# ALINHAMENTO_UNIC.net
KiCad netlist of a schematic drawn in EAGLE
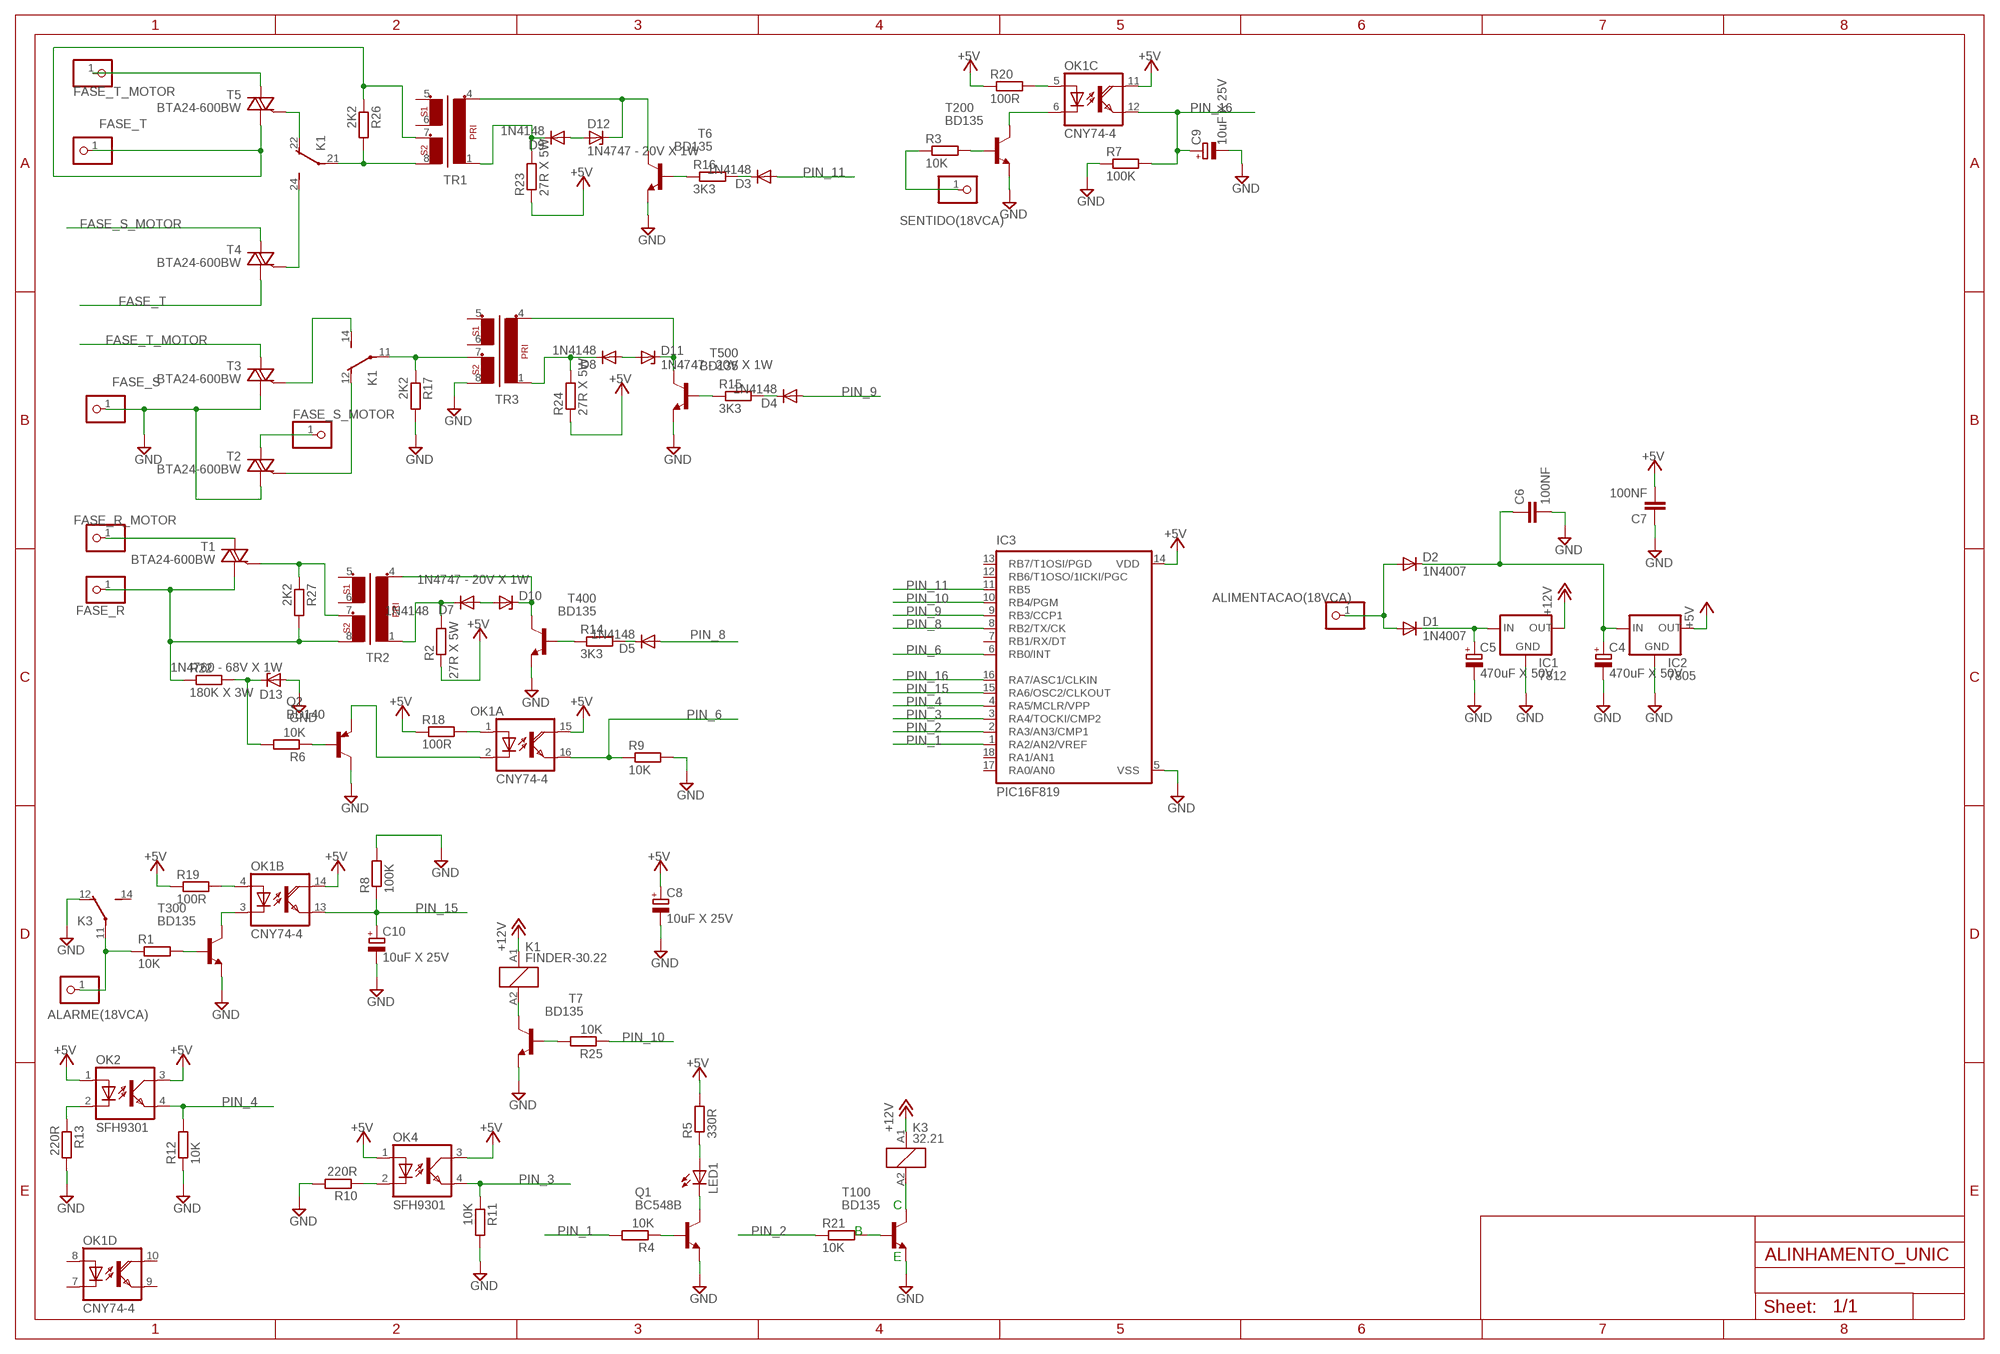
[diagram p0: schematic, sheet 1]

(export (version "E")
  (design (tool "Eeschema 10.0.6"))
  (components
    (comp (ref "ALARME(18VCA)")
      (value "PINHD-1X1")
      (footprint "eagle-import:1X01")
      (libsource (lib "eagle-import") (part "PINHD-1X1"))
    )
    (comp (ref "ALIMENTACAO(18VCA)")
      (value "PINHD-1X1")
      (footprint "eagle-import:1X01")
      (libsource (lib "eagle-import") (part "PINHD-1X1"))
    )
    (comp (ref "C4")
      (value "470uF X 50V")
      (footprint "eagle-import:E5-13")
      (libsource (lib "eagle-import") (part "CPOL-EUE5-13"))
    )
    (comp (ref "C5")
      (value "470uF X 50V")
      (footprint "eagle-import:E5-13")
      (libsource (lib "eagle-import") (part "CPOL-EUE5-13"))
    )
    (comp (ref "C6")
      (value "100NF")
      (footprint "eagle-import:C050-025X075")
      (libsource (lib "eagle-import") (part "C-EU050-025X075"))
    )
    (comp (ref "C7")
      (value "100NF")
      (footprint "eagle-import:C050-025X075")
      (libsource (lib "eagle-import") (part "C-EU050-025X075"))
    )
    (comp (ref "C8")
      (value "10uF X 25V")
      (footprint "eagle-import:E2-5")
      (libsource (lib "eagle-import") (part "CPOL-EUE2-5"))
    )
    (comp (ref "C9")
      (value "10uF X 25V")
      (footprint "eagle-import:E2-5")
      (libsource (lib "eagle-import") (part "CPOL-EUE2-5"))
    )
    (comp (ref "C10")
      (value "10uF X 25V")
      (footprint "eagle-import:E2-5")
      (libsource (lib "eagle-import") (part "CPOL-EUE2-5"))
    )
    (comp (ref "D1")
      (value "1N4007")
      (footprint "eagle-import:DO41-10")
      (libsource (lib "eagle-import") (part "1N4004"))
    )
    (comp (ref "D2")
      (value "1N4007")
      (footprint "eagle-import:DO41-10")
      (libsource (lib "eagle-import") (part "1N4004"))
    )
    (comp (ref "D3")
      (value "1N4148")
      (footprint "eagle-import:DO35-10")
      (libsource (lib "eagle-import") (part "1N4148DO35-10"))
    )
    (comp (ref "D4")
      (value "1N4148")
      (footprint "eagle-import:DO35-10")
      (libsource (lib "eagle-import") (part "1N4148DO35-10"))
    )
    (comp (ref "D5")
      (value "1N4148")
      (footprint "eagle-import:DO35-10")
      (libsource (lib "eagle-import") (part "1N4148DO35-10"))
    )
    (comp (ref "D7")
      (value "1N4148")
      (footprint "eagle-import:DO35-10")
      (libsource (lib "eagle-import") (part "1N4148DO35-10"))
    )
    (comp (ref "D8")
      (value "1N4148")
      (footprint "eagle-import:DO35-10")
      (libsource (lib "eagle-import") (part "1N4148DO35-10"))
    )
    (comp (ref "D9")
      (value "1N4148")
      (footprint "eagle-import:DO35-10")
      (libsource (lib "eagle-import") (part "1N4148DO35-10"))
    )
    (comp (ref "D10")
      (value "1N4747 - 20V X 1W")
      (footprint "eagle-import:DO41Z10")
      (libsource (lib "eagle-import") (part "1N4728"))
    )
    (comp (ref "D11")
      (value "1N4747 - 20V X 1W")
      (footprint "eagle-import:DO41Z10")
      (libsource (lib "eagle-import") (part "1N4728"))
    )
    (comp (ref "D12")
      (value "1N4747 - 20V X 1W")
      (footprint "eagle-import:DO41Z10")
      (libsource (lib "eagle-import") (part "1N4728"))
    )
    (comp (ref "D13")
      (value "1N4760 - 68V X 1W")
      (footprint "eagle-import:DO41Z10")
      (libsource (lib "eagle-import") (part "1N4728"))
    )
    (comp (ref "FASE_R")
      (value "PINHD-1X1")
      (footprint "eagle-import:1X01")
      (libsource (lib "eagle-import") (part "PINHD-1X1"))
    )
    (comp (ref "FASE_R_MOTOR")
      (value "PINHD-1X1")
      (footprint "eagle-import:1X01")
      (libsource (lib "eagle-import") (part "PINHD-1X1"))
    )
    (comp (ref "FASE_S")
      (value "PINHD-1X1")
      (footprint "eagle-import:1X01")
      (libsource (lib "eagle-import") (part "PINHD-1X1"))
    )
    (comp (ref "FASE_S_MOTOR")
      (value "PINHD-1X1")
      (footprint "eagle-import:1X01")
      (libsource (lib "eagle-import") (part "PINHD-1X1"))
    )
    (comp (ref "FASE_T")
      (value "PINHD-1X1")
      (footprint "eagle-import:1X01")
      (libsource (lib "eagle-import") (part "PINHD-1X1"))
    )
    (comp (ref "FASE_T_MOTOR")
      (value "PINHD-1X1")
      (footprint "eagle-import:1X01")
      (libsource (lib "eagle-import") (part "PINHD-1X1"))
    )
    (comp (ref "IC1")
      (value "7812")
      (footprint "eagle-import:78MXXS")
      (libsource (lib "eagle-import") (part "78MXXS"))
    )
    (comp (ref "IC2")
      (value "7805")
      (footprint "eagle-import:78MXXS")
      (libsource (lib "eagle-import") (part "78MXXS"))
    )
    (comp (ref "IC3")
      (value "PIC16F819")
      (footprint "eagle-import:DIL18")
      (libsource (lib "eagle-import") (part "PIC16F627P"))
    )
    (comp (ref "K1")
      (value "FINDER-30.22")
      (footprint "eagle-import:FINDER-30.22")
      (libsource (lib "eagle-import") (part "FINDER-30.22"))
    )
    (comp (ref "K3")
      (value "32.21")
      (footprint "eagle-import:RP51")
      (libsource (lib "eagle-import") (part "32.21"))
    )
    (comp (ref "LED1")
      (value "LED5MM")
      (footprint "eagle-import:LED5MM")
      (libsource (lib "eagle-import") (part "LED5MM"))
    )
    (comp (ref "OK1")
      (value "CNY74-4")
      (footprint "eagle-import:DIL16")
      (libsource (lib "eagle-import") (part "ILQ30"))
    )
    (comp (ref "OK2")
      (value "SFH9301")
      (footprint "eagle-import:SFH9301")
      (libsource (lib "eagle-import") (part "SFH9301"))
    )
    (comp (ref "OK4")
      (value "SFH9301")
      (footprint "eagle-import:SFH9301")
      (libsource (lib "eagle-import") (part "SFH9301"))
    )
    (comp (ref "Q1")
      (value "BC548B")
      (footprint "eagle-import:TO92-EBC")
      (libsource (lib "eagle-import") (part "BC548B"))
    )
    (comp (ref "Q2")
      (value "BD140")
      (footprint "eagle-import:TO126")
      (libsource (lib "eagle-import") (part "BD140"))
    )
    (comp (ref "R1")
      (value "10K")
      (footprint "eagle-import:0207_10")
      (libsource (lib "eagle-import") (part "R-EU_0207/10"))
    )
    (comp (ref "R2")
      (value "27R X 5W")
      (footprint "eagle-import:0617_22")
      (libsource (lib "eagle-import") (part "R-EU_0617/22"))
    )
    (comp (ref "R3")
      (value "10K")
      (footprint "eagle-import:0207_10")
      (libsource (lib "eagle-import") (part "R-EU_0207/10"))
    )
    (comp (ref "R4")
      (value "10K")
      (footprint "eagle-import:0207_10")
      (libsource (lib "eagle-import") (part "R-EU_0207/10"))
    )
    (comp (ref "R5")
      (value "330R")
      (footprint "eagle-import:0207_10")
      (libsource (lib "eagle-import") (part "R-EU_0207/10"))
    )
    (comp (ref "R6")
      (value "10K")
      (footprint "eagle-import:0207_10")
      (libsource (lib "eagle-import") (part "R-EU_0207/10"))
    )
    (comp (ref "R7")
      (value "100K")
      (footprint "eagle-import:0207_10")
      (libsource (lib "eagle-import") (part "R-EU_0207/10"))
    )
    (comp (ref "R8")
      (value "100K")
      (footprint "eagle-import:0207_10")
      (libsource (lib "eagle-import") (part "R-EU_0207/10"))
    )
    (comp (ref "R9")
      (value "10K")
      (footprint "eagle-import:0207_10")
      (libsource (lib "eagle-import") (part "R-EU_0207/10"))
    )
    (comp (ref "R10")
      (value "220R")
      (footprint "eagle-import:0207_10")
      (libsource (lib "eagle-import") (part "R-EU_0207/10"))
    )
    (comp (ref "R11")
      (value "10K")
      (footprint "eagle-import:0207_10")
      (libsource (lib "eagle-import") (part "R-EU_0207/10"))
    )
    (comp (ref "R12")
      (value "10K")
      (footprint "eagle-import:0207_10")
      (libsource (lib "eagle-import") (part "R-EU_0207/10"))
    )
    (comp (ref "R13")
      (value "220R")
      (footprint "eagle-import:0207_10")
      (libsource (lib "eagle-import") (part "R-EU_0207/10"))
    )
    (comp (ref "R14")
      (value "3K3")
      (footprint "eagle-import:0207_10")
      (libsource (lib "eagle-import") (part "R-EU_0207/10"))
    )
    (comp (ref "R15")
      (value "3K3")
      (footprint "eagle-import:0207_10")
      (libsource (lib "eagle-import") (part "R-EU_0207/10"))
    )
    (comp (ref "R16")
      (value "3K3")
      (footprint "eagle-import:0207_10")
      (libsource (lib "eagle-import") (part "R-EU_0207/10"))
    )
    (comp (ref "R17")
      (value "2K2")
      (footprint "eagle-import:0207_10")
      (libsource (lib "eagle-import") (part "R-EU_0207/10"))
    )
    (comp (ref "R18")
      (value "100R")
      (footprint "eagle-import:0207_10")
      (libsource (lib "eagle-import") (part "R-EU_0207/10"))
    )
    (comp (ref "R19")
      (value "100R")
      (footprint "eagle-import:0207_10")
      (libsource (lib "eagle-import") (part "R-EU_0207/10"))
    )
    (comp (ref "R20")
      (value "100R")
      (footprint "eagle-import:0207_10")
      (libsource (lib "eagle-import") (part "R-EU_0207/10"))
    )
    (comp (ref "R21")
      (value "10K")
      (footprint "eagle-import:0207_10")
      (libsource (lib "eagle-import") (part "R-EU_0207/10"))
    )
    (comp (ref "R22")
      (value "180K X 3W")
      (footprint "eagle-import:0617_22")
      (libsource (lib "eagle-import") (part "R-EU_0617/22"))
    )
    (comp (ref "R23")
      (value "27R X 5W")
      (footprint "eagle-import:0617_22")
      (libsource (lib "eagle-import") (part "R-EU_0617/22"))
    )
    (comp (ref "R24")
      (value "27R X 5W")
      (footprint "eagle-import:0617_22")
      (libsource (lib "eagle-import") (part "R-EU_0617/22"))
    )
    (comp (ref "R25")
      (value "10K")
      (footprint "eagle-import:0207_10")
      (libsource (lib "eagle-import") (part "R-EU_0207/10"))
    )
    (comp (ref "R26")
      (value "2K2")
      (footprint "eagle-import:0207_10")
      (libsource (lib "eagle-import") (part "R-EU_0207/10"))
    )
    (comp (ref "R27")
      (value "2K2")
      (footprint "eagle-import:0207_10")
      (libsource (lib "eagle-import") (part "R-EU_0207/10"))
    )
    (comp (ref "SENTIDO(18VCA)")
      (value "PINHD-1X1")
      (footprint "eagle-import:1X01")
      (libsource (lib "eagle-import") (part "PINHD-1X1"))
    )
    (comp (ref "T1")
      (value "BTA24-600BW")
      (footprint "eagle-import:TOP3S-1")
      (libsource (lib "eagle-import") (part "BTA26-V"))
    )
    (comp (ref "T2")
      (value "BTA24-600BW")
      (footprint "eagle-import:TOP3S-1")
      (libsource (lib "eagle-import") (part "BTA26-V"))
    )
    (comp (ref "T3")
      (value "BTA24-600BW")
      (footprint "eagle-import:TOP3S-1")
      (libsource (lib "eagle-import") (part "BTA26-V"))
    )
    (comp (ref "T4")
      (value "BTA24-600BW")
      (footprint "eagle-import:TOP3S-1")
      (libsource (lib "eagle-import") (part "BTA26-V"))
    )
    (comp (ref "T5")
      (value "BTA24-600BW")
      (footprint "eagle-import:TOP3S-1")
      (libsource (lib "eagle-import") (part "BTA26-V"))
    )
    (comp (ref "T6")
      (value "BD135")
      (footprint "eagle-import:TO126")
      (libsource (lib "eagle-import") (part "BD139"))
    )
    (comp (ref "T7")
      (value "BD135")
      (footprint "eagle-import:TO126")
      (libsource (lib "eagle-import") (part "BD139"))
    )
    (comp (ref "T100")
      (value "BD135")
      (footprint "eagle-import:TO126")
      (libsource (lib "eagle-import") (part "BD139"))
    )
    (comp (ref "T200")
      (value "BD135")
      (footprint "eagle-import:TO126")
      (libsource (lib "eagle-import") (part "BD139"))
    )
    (comp (ref "T300")
      (value "BD135")
      (footprint "eagle-import:TO126")
      (libsource (lib "eagle-import") (part "BD139"))
    )
    (comp (ref "T400")
      (value "BD135")
      (footprint "eagle-import:TO126")
      (libsource (lib "eagle-import") (part "BD139"))
    )
    (comp (ref "T500")
      (value "BD135")
      (footprint "eagle-import:TO126")
      (libsource (lib "eagle-import") (part "BD139"))
    )
    (comp (ref "TR1")
      (value "EE20-2")
      (footprint "eagle-import:EE20-2")
      (libsource (lib "eagle-import") (part "EE20-2"))
    )
    (comp (ref "TR2")
      (value "EE20-2")
      (footprint "eagle-import:EE20-2")
      (libsource (lib "eagle-import") (part "EE20-2"))
    )
    (comp (ref "TR3")
      (value "EE20-2")
      (footprint "eagle-import:EE20-2")
      (libsource (lib "eagle-import") (part "EE20-2"))
    )
  )
  (nets
    (net (code "1") (name "+5V") (class "Default")
      (node (ref "C7") (pin "2") (pinfunction "2_2") (pintype "passive"))
      (node (ref "C8") (pin "+") (pinfunction "+_+") (pintype "passive"))
      (node (ref "IC2") (pin "OUT") (pinfunction "OUT_OUT") (pintype "passive"))
      (node (ref "IC3") (pin "14") (pinfunction "VDD_14") (pintype "power_in"))
      (node (ref "OK1") (pin "11") (pinfunction "COL_11") (pintype "passive"))
      (node (ref "OK1") (pin "14") (pinfunction "COL_14") (pintype "passive"))
      (node (ref "OK1") (pin "15") (pinfunction "COL_15") (pintype "passive"))
      (node (ref "OK2") (pin "1") (pinfunction "A_1") (pintype "passive"))
      (node (ref "OK2") (pin "3") (pinfunction "COL_3") (pintype "passive"))
      (node (ref "OK4") (pin "1") (pinfunction "A_1") (pintype "passive"))
      (node (ref "OK4") (pin "3") (pinfunction "COL_3") (pintype "passive"))
      (node (ref "R18") (pin "1") (pinfunction "1_1") (pintype "passive"))
      (node (ref "R19") (pin "1") (pinfunction "1_1") (pintype "passive"))
      (node (ref "R2") (pin "1") (pinfunction "1_1") (pintype "passive"))
      (node (ref "R20") (pin "1") (pinfunction "1_1") (pintype "passive"))
      (node (ref "R23") (pin "1") (pinfunction "1_1") (pintype "passive"))
      (node (ref "R24") (pin "1") (pinfunction "1_1") (pintype "passive"))
      (node (ref "R5") (pin "2") (pinfunction "2_2") (pintype "passive"))
    )
    (net (code "2") (name "+12V") (class "Default")
      (node (ref "IC1") (pin "OUT") (pinfunction "OUT_OUT") (pintype "passive"))
      (node (ref "K1") (pin "A1") (pinfunction "1_A1") (pintype "passive"))
      (node (ref "K3") (pin "A1") (pinfunction "1_A1") (pintype "passive"))
    )
    (net (code "3") (name "/FASE_S_MOTOR") (class "Default")
      (node (ref "FASE_S_MOTOR") (pin "1") (pinfunction "1_1") (pintype "passive"))
      (node (ref "T2") (pin "A2") (pinfunction "A2_A2") (pintype "passive"))
      (node (ref "T4") (pin "A2") (pinfunction "A2_A2") (pintype "passive"))
    )
    (net (code "4") (name "/FASE_T") (class "Default")
      (node (ref "FASE_T") (pin "1") (pinfunction "1_1") (pintype "passive"))
      (node (ref "R26") (pin "1") (pinfunction "1_1") (pintype "passive"))
      (node (ref "T4") (pin "A1") (pinfunction "A1_A1") (pintype "passive"))
      (node (ref "T5") (pin "A1") (pinfunction "A1_A1") (pintype "passive"))
      (node (ref "TR1") (pin "7") (pinfunction "5_7") (pintype "passive"))
    )
    (net (code "5") (name "/FASE_T_MOTOR") (class "Default")
      (node (ref "FASE_T_MOTOR") (pin "1") (pinfunction "1_1") (pintype "passive"))
      (node (ref "T3") (pin "A2") (pinfunction "A2_A2") (pintype "passive"))
      (node (ref "T5") (pin "A2") (pinfunction "A2_A2") (pintype "passive"))
    )
    (net (code "6") (name "/PIN_1") (class "Default")
      (node (ref "IC3") (pin "1") (pinfunction "RA2/AN2/VREF_1") (pintype "bidirectional"))
      (node (ref "R4") (pin "2") (pinfunction "2_2") (pintype "passive"))
    )
    (net (code "7") (name "/PIN_2") (class "Default")
      (node (ref "IC3") (pin "2") (pinfunction "RA3/AN3/CMP1_2") (pintype "bidirectional"))
      (node (ref "R21") (pin "1") (pinfunction "1_1") (pintype "passive"))
    )
    (net (code "8") (name "/PIN_3") (class "Default")
      (node (ref "IC3") (pin "3") (pinfunction "RA4/TOCKI/CMP2_3") (pintype "bidirectional"))
      (node (ref "OK4") (pin "4") (pinfunction "EMIT_4") (pintype "passive"))
      (node (ref "R11") (pin "1") (pinfunction "1_1") (pintype "passive"))
    )
    (net (code "9") (name "/PIN_4") (class "Default")
      (node (ref "IC3") (pin "4") (pinfunction "RA5/MCLR/VPP_4") (pintype "input"))
      (node (ref "OK2") (pin "4") (pinfunction "EMIT_4") (pintype "passive"))
      (node (ref "R12") (pin "2") (pinfunction "2_2") (pintype "passive"))
    )
    (net (code "10") (name "/PIN_6") (class "Default")
      (node (ref "IC3") (pin "6") (pinfunction "RB0/INT_6") (pintype "bidirectional"))
      (node (ref "OK1") (pin "16") (pinfunction "EMI_16") (pintype "passive"))
      (node (ref "R9") (pin "1") (pinfunction "1_1") (pintype "passive"))
    )
    (net (code "11") (name "/PIN_8") (class "Default")
      (node (ref "D5") (pin "A") (pinfunction "A_A") (pintype "passive"))
      (node (ref "IC3") (pin "8") (pinfunction "RB2/TX/CK_8") (pintype "bidirectional"))
    )
    (net (code "12") (name "/PIN_9") (class "Default")
      (node (ref "D4") (pin "A") (pinfunction "A_A") (pintype "passive"))
      (node (ref "IC3") (pin "9") (pinfunction "RB3/CCP1_9") (pintype "bidirectional"))
    )
    (net (code "13") (name "/PIN_10") (class "Default")
      (node (ref "IC3") (pin "10") (pinfunction "RB4/PGM_10") (pintype "bidirectional"))
      (node (ref "R25") (pin "1") (pinfunction "1_1") (pintype "passive"))
    )
    (net (code "14") (name "/PIN_11") (class "Default")
      (node (ref "D3") (pin "A") (pinfunction "A_A") (pintype "passive"))
      (node (ref "IC3") (pin "11") (pinfunction "RB5_11") (pintype "bidirectional"))
    )
    (net (code "15") (name "/PIN_15") (class "Default")
      (node (ref "C10") (pin "+") (pinfunction "+_+") (pintype "passive"))
      (node (ref "IC3") (pin "15") (pinfunction "RA6/OSC2/CLKOUT_15") (pintype "bidirectional"))
      (node (ref "OK1") (pin "13") (pinfunction "EMI_13") (pintype "passive"))
      (node (ref "R8") (pin "1") (pinfunction "1_1") (pintype "passive"))
    )
    (net (code "16") (name "/PIN_16") (class "Default")
      (node (ref "C9") (pin "+") (pinfunction "+_+") (pintype "passive"))
      (node (ref "IC3") (pin "16") (pinfunction "RA7/ASC1/CLKIN_16") (pintype "bidirectional"))
      (node (ref "OK1") (pin "12") (pinfunction "EMI_12") (pintype "passive"))
      (node (ref "R7") (pin "2") (pinfunction "2_2") (pintype "passive"))
    )
    (net (code "17") (name "GND") (class "Default")
      (node (ref "C10") (pin "-") (pinfunction "-_-") (pintype "passive"))
      (node (ref "C4") (pin "-") (pinfunction "-_-") (pintype "passive"))
      (node (ref "C5") (pin "-") (pinfunction "-_-") (pintype "passive"))
      (node (ref "C6") (pin "2") (pinfunction "2_2") (pintype "passive"))
      (node (ref "C7") (pin "1") (pinfunction "1_1") (pintype "passive"))
      (node (ref "C8") (pin "-") (pinfunction "-_-") (pintype "passive"))
      (node (ref "C9") (pin "-") (pinfunction "-_-") (pintype "passive"))
      (node (ref "D13") (pin "A") (pinfunction "A_A") (pintype "passive"))
      (node (ref "FASE_S") (pin "1") (pinfunction "1_1") (pintype "passive"))
      (node (ref "IC1") (pin "GND") (pinfunction "GND_GND") (pintype "input"))
      (node (ref "IC2") (pin "GND") (pinfunction "GND_GND") (pintype "input"))
      (node (ref "IC3") (pin "5") (pinfunction "VSS_5") (pintype "power_in"))
      (node (ref "K3") (pin "12") (pinfunction "O_12") (pintype "passive"))
      (node (ref "Q1") (pin "E") (pinfunction "E_E") (pintype "passive"))
      (node (ref "Q2") (pin "2") (pinfunction "C_2") (pintype "passive"))
      (node (ref "R10") (pin "2") (pinfunction "2_2") (pintype "passive"))
      (node (ref "R11") (pin "2") (pinfunction "2_2") (pintype "passive"))
      (node (ref "R12") (pin "1") (pinfunction "1_1") (pintype "passive"))
      (node (ref "R13") (pin "2") (pinfunction "2_2") (pintype "passive"))
      (node (ref "R17") (pin "2") (pinfunction "2_2") (pintype "passive"))
      (node (ref "R7") (pin "1") (pinfunction "1_1") (pintype "passive"))
      (node (ref "R8") (pin "2") (pinfunction "2_2") (pintype "passive"))
      (node (ref "R9") (pin "2") (pinfunction "2_2") (pintype "passive"))
      (node (ref "T100") (pin "1") (pinfunction "E_1") (pintype "passive"))
      (node (ref "T2") (pin "A1") (pinfunction "A1_A1") (pintype "passive"))
      (node (ref "T200") (pin "1") (pinfunction "E_1") (pintype "passive"))
      (node (ref "T3") (pin "A1") (pinfunction "A1_A1") (pintype "passive"))
      (node (ref "T300") (pin "1") (pinfunction "E_1") (pintype "passive"))
      (node (ref "T400") (pin "1") (pinfunction "E_1") (pintype "passive"))
      (node (ref "T500") (pin "1") (pinfunction "E_1") (pintype "passive"))
      (node (ref "T6") (pin "1") (pinfunction "E_1") (pintype "passive"))
      (node (ref "T7") (pin "1") (pinfunction "E_1") (pintype "passive"))
      (node (ref "TR3") (pin "8") (pinfunction "6_8") (pintype "passive"))
    )
    (net (code "18") (name "Net-(ALIMENTACAO(18VCA)-Pad1)") (class "Default")
      (node (ref "ALIMENTACAO(18VCA)") (pin "1") (pinfunction "1_1") (pintype "passive"))
      (node (ref "D1") (pin "A") (pinfunction "A_A") (pintype "passive"))
      (node (ref "D2") (pin "A") (pinfunction "A_A") (pintype "passive"))
    )
    (net (code "19") (name "Net-(C4-Pad+)") (class "Default")
      (node (ref "C4") (pin "+") (pinfunction "+_+") (pintype "passive"))
      (node (ref "C6") (pin "1") (pinfunction "1_1") (pintype "passive"))
      (node (ref "D2") (pin "C") (pinfunction "C_C") (pintype "passive"))
      (node (ref "IC2") (pin "IN") (pinfunction "IN_IN") (pintype "input"))
    )
    (net (code "20") (name "Net-(C5-Pad+)") (class "Default")
      (node (ref "C5") (pin "+") (pinfunction "+_+") (pintype "passive"))
      (node (ref "D1") (pin "C") (pinfunction "C_C") (pintype "passive"))
      (node (ref "IC1") (pin "IN") (pinfunction "IN_IN") (pintype "input"))
    )
    (net (code "21") (name "Net-(D3-PadC)") (class "Default")
      (node (ref "D3") (pin "C") (pinfunction "C_C") (pintype "passive"))
      (node (ref "R16") (pin "2") (pinfunction "2_2") (pintype "passive"))
    )
    (net (code "22") (name "Net-(D4-PadC)") (class "Default")
      (node (ref "D4") (pin "C") (pinfunction "C_C") (pintype "passive"))
      (node (ref "R15") (pin "2") (pinfunction "2_2") (pintype "passive"))
    )
    (net (code "23") (name "Net-(D5-PadC)") (class "Default")
      (node (ref "D5") (pin "C") (pinfunction "C_C") (pintype "passive"))
      (node (ref "R14") (pin "2") (pinfunction "2_2") (pintype "passive"))
    )
    (net (code "24") (name "Net-(D7-PadC)") (class "Default")
      (node (ref "D7") (pin "C") (pinfunction "C_C") (pintype "passive"))
      (node (ref "R2") (pin "2") (pinfunction "2_2") (pintype "passive"))
      (node (ref "TR2") (pin "1") (pinfunction "1_1") (pintype "passive"))
    )
    (net (code "25") (name "Net-(D8-PadC)") (class "Default")
      (node (ref "D8") (pin "C") (pinfunction "C_C") (pintype "passive"))
      (node (ref "R24") (pin "2") (pinfunction "2_2") (pintype "passive"))
      (node (ref "TR3") (pin "1") (pinfunction "1_1") (pintype "passive"))
    )
    (net (code "26") (name "Net-(D9-PadC)") (class "Default")
      (node (ref "D9") (pin "C") (pinfunction "C_C") (pintype "passive"))
      (node (ref "R23") (pin "2") (pinfunction "2_2") (pintype "passive"))
      (node (ref "TR1") (pin "1") (pinfunction "1_1") (pintype "passive"))
    )
    (net (code "27") (name "Net-(D10-PadA)") (class "Default")
      (node (ref "D10") (pin "A") (pinfunction "A_A") (pintype "passive"))
      (node (ref "D7") (pin "A") (pinfunction "A_A") (pintype "passive"))
    )
    (net (code "28") (name "Net-(D11-PadA)") (class "Default")
      (node (ref "D11") (pin "A") (pinfunction "A_A") (pintype "passive"))
      (node (ref "D8") (pin "A") (pinfunction "A_A") (pintype "passive"))
    )
    (net (code "29") (name "Net-(D12-PadA)") (class "Default")
      (node (ref "D12") (pin "A") (pinfunction "A_A") (pintype "passive"))
      (node (ref "D9") (pin "A") (pinfunction "A_A") (pintype "passive"))
    )
    (net (code "30") (name "Net-(D13-PadC)") (class "Default")
      (node (ref "D13") (pin "C") (pinfunction "C_C") (pintype "passive"))
      (node (ref "R22") (pin "2") (pinfunction "2_2") (pintype "passive"))
      (node (ref "R6") (pin "2") (pinfunction "2_2") (pintype "passive"))
    )
    (net (code "31") (name "Net-(FASE_R_MOTOR-Pad1)") (class "Default")
      (node (ref "FASE_R_MOTOR") (pin "1") (pinfunction "1_1") (pintype "passive"))
      (node (ref "T1") (pin "A2") (pinfunction "A2_A2") (pintype "passive"))
    )
    (net (code "32") (name "Net-(K1A-O)") (class "Default")
      (node (ref "K1") (pin "12") (pinfunction "O_12") (pintype "passive"))
      (node (ref "T2") (pin "G") (pinfunction "G_G") (pintype "passive"))
    )
    (net (code "33") (name "Net-(K1A-P)") (class "Default")
      (node (ref "K1") (pin "11") (pinfunction "P_11") (pintype "passive"))
      (node (ref "R17") (pin "1") (pinfunction "1_1") (pintype "passive"))
      (node (ref "TR3") (pin "7") (pinfunction "5_7") (pintype "passive"))
    )
    (net (code "34") (name "Net-(K1A-S)") (class "Default")
      (node (ref "K1") (pin "14") (pinfunction "S_14") (pintype "passive"))
      (node (ref "T3") (pin "G") (pinfunction "G_G") (pintype "passive"))
    )
    (net (code "35") (name "Net-(K1B-O)") (class "Default")
      (node (ref "K1") (pin "22") (pinfunction "O_22") (pintype "passive"))
      (node (ref "T5") (pin "G") (pinfunction "G_G") (pintype "passive"))
    )
    (net (code "36") (name "Net-(K1B-P)") (class "Default")
      (node (ref "K1") (pin "21") (pinfunction "P_21") (pintype "passive"))
      (node (ref "R26") (pin "2") (pinfunction "2_2") (pintype "passive"))
      (node (ref "TR1") (pin "8") (pinfunction "6_8") (pintype "passive"))
    )
    (net (code "37") (name "Net-(K1B-S)") (class "Default")
      (node (ref "K1") (pin "24") (pinfunction "S_24") (pintype "passive"))
      (node (ref "T4") (pin "G") (pinfunction "G_G") (pintype "passive"))
    )
    (net (code "38") (name "Net-(K1C-2)") (class "Default")
      (node (ref "K1") (pin "A2") (pinfunction "2_A2") (pintype "passive"))
      (node (ref "T7") (pin "2") (pinfunction "C_2") (pintype "passive"))
    )
    (net (code "39") (name "Net-(K3A-2)") (class "Default")
      (node (ref "K3") (pin "A2") (pinfunction "2_A2") (pintype "passive"))
      (node (ref "T100") (pin "2") (pinfunction "C_2") (pintype "passive"))
    )
    (net (code "40") (name "Net-(K3B-P)") (class "Default")
      (node (ref "ALARME(18VCA)") (pin "1") (pinfunction "1_1") (pintype "passive"))
      (node (ref "K3") (pin "11") (pinfunction "P_11") (pintype "passive"))
      (node (ref "R1") (pin "1") (pinfunction "1_1") (pintype "passive"))
    )
    (net (code "41") (name "Net-(LED1-C)") (class "Default")
      (node (ref "LED1") (pin "K") (pinfunction "C_K") (pintype "passive"))
      (node (ref "Q1") (pin "C") (pinfunction "C_C") (pintype "passive"))
    )
    (net (code "42") (name "Net-(LED1-PadA)") (class "Default")
      (node (ref "LED1") (pin "A") (pinfunction "A_A") (pintype "passive"))
      (node (ref "R5") (pin "1") (pinfunction "1_1") (pintype "passive"))
    )
    (net (code "43") (name "Net-(OK1A-A)") (class "Default")
      (node (ref "OK1") (pin "1") (pinfunction "A_1") (pintype "passive"))
      (node (ref "R18") (pin "2") (pinfunction "2_2") (pintype "passive"))
    )
    (net (code "44") (name "Net-(OK1A-C)") (class "Default")
      (node (ref "OK1") (pin "2") (pinfunction "C_2") (pintype "passive"))
      (node (ref "Q2") (pin "1") (pinfunction "E_1") (pintype "passive"))
    )
    (net (code "45") (name "Net-(OK1B-A)") (class "Default")
      (node (ref "OK1") (pin "4") (pinfunction "A_4") (pintype "passive"))
      (node (ref "R19") (pin "2") (pinfunction "2_2") (pintype "passive"))
    )
    (net (code "46") (name "Net-(OK1B-C)") (class "Default")
      (node (ref "OK1") (pin "3") (pinfunction "C_3") (pintype "passive"))
      (node (ref "T300") (pin "2") (pinfunction "C_2") (pintype "passive"))
    )
    (net (code "47") (name "Net-(OK1C-A)") (class "Default")
      (node (ref "OK1") (pin "5") (pinfunction "A_5") (pintype "passive"))
      (node (ref "R20") (pin "2") (pinfunction "2_2") (pintype "passive"))
    )
    (net (code "48") (name "Net-(OK1C-C)") (class "Default")
      (node (ref "OK1") (pin "6") (pinfunction "C_6") (pintype "passive"))
      (node (ref "T200") (pin "2") (pinfunction "C_2") (pintype "passive"))
    )
    (net (code "49") (name "Net-(OK2-C)") (class "Default")
      (node (ref "OK2") (pin "2") (pinfunction "C_2") (pintype "passive"))
      (node (ref "R13") (pin "1") (pinfunction "1_1") (pintype "passive"))
    )
    (net (code "50") (name "Net-(OK4-C)") (class "Default")
      (node (ref "OK4") (pin "2") (pinfunction "C_2") (pintype "passive"))
      (node (ref "R10") (pin "1") (pinfunction "1_1") (pintype "passive"))
    )
    (net (code "51") (name "Net-(Q1-PadB)") (class "Default")
      (node (ref "Q1") (pin "B") (pinfunction "B_B") (pintype "passive"))
      (node (ref "R4") (pin "1") (pinfunction "1_1") (pintype "passive"))
    )
    (net (code "52") (name "Net-(Q2-B)") (class "Default")
      (node (ref "Q2") (pin "3") (pinfunction "B_3") (pintype "passive"))
      (node (ref "R6") (pin "1") (pinfunction "1_1") (pintype "passive"))
    )
    (net (code "53") (name "Net-(R3-Pad1)") (class "Default")
      (node (ref "R3") (pin "1") (pinfunction "1_1") (pintype "passive"))
      (node (ref "SENTIDO(18VCA)") (pin "1") (pinfunction "1_1") (pintype "passive"))
    )
    (net (code "54") (name "Net-(T6-B)") (class "Default")
      (node (ref "R16") (pin "1") (pinfunction "1_1") (pintype "passive"))
      (node (ref "T6") (pin "3") (pinfunction "B_3") (pintype "passive"))
    )
    (net (code "55") (name "Net-(T6-C)") (class "Default")
      (node (ref "D12") (pin "C") (pinfunction "C_C") (pintype "passive"))
      (node (ref "T6") (pin "2") (pinfunction "C_2") (pintype "passive"))
      (node (ref "TR1") (pin "4") (pinfunction "2_4") (pintype "passive"))
    )
    (net (code "56") (name "Net-(T7-B)") (class "Default")
      (node (ref "R25") (pin "2") (pinfunction "2_2") (pintype "passive"))
      (node (ref "T7") (pin "3") (pinfunction "B_3") (pintype "passive"))
    )
    (net (code "57") (name "Net-(T100-B)") (class "Default")
      (node (ref "R21") (pin "2") (pinfunction "2_2") (pintype "passive"))
      (node (ref "T100") (pin "3") (pinfunction "B_3") (pintype "passive"))
    )
    (net (code "58") (name "Net-(T200-B)") (class "Default")
      (node (ref "R3") (pin "2") (pinfunction "2_2") (pintype "passive"))
      (node (ref "T200") (pin "3") (pinfunction "B_3") (pintype "passive"))
    )
    (net (code "59") (name "Net-(T300-B)") (class "Default")
      (node (ref "R1") (pin "2") (pinfunction "2_2") (pintype "passive"))
      (node (ref "T300") (pin "3") (pinfunction "B_3") (pintype "passive"))
    )
    (net (code "60") (name "Net-(T400-B)") (class "Default")
      (node (ref "R14") (pin "1") (pinfunction "1_1") (pintype "passive"))
      (node (ref "T400") (pin "3") (pinfunction "B_3") (pintype "passive"))
    )
    (net (code "61") (name "Net-(T400-C)") (class "Default")
      (node (ref "D10") (pin "C") (pinfunction "C_C") (pintype "passive"))
      (node (ref "T400") (pin "2") (pinfunction "C_2") (pintype "passive"))
      (node (ref "TR2") (pin "4") (pinfunction "2_4") (pintype "passive"))
    )
    (net (code "62") (name "Net-(T500-B)") (class "Default")
      (node (ref "R15") (pin "1") (pinfunction "1_1") (pintype "passive"))
      (node (ref "T500") (pin "3") (pinfunction "B_3") (pintype "passive"))
    )
    (net (code "63") (name "Net-(T500-C)") (class "Default")
      (node (ref "D11") (pin "C") (pinfunction "C_C") (pintype "passive"))
      (node (ref "T500") (pin "2") (pinfunction "C_2") (pintype "passive"))
      (node (ref "TR3") (pin "4") (pinfunction "2_4") (pintype "passive"))
    )
    (net (code "64") (name "Net-(TR2-5)") (class "Default")
      (node (ref "R27") (pin "1") (pinfunction "1_1") (pintype "passive"))
      (node (ref "T1") (pin "G") (pinfunction "G_G") (pintype "passive"))
      (node (ref "TR2") (pin "7") (pinfunction "5_7") (pintype "passive"))
    )
    (net (code "65") (name "Net-(TR2-6)") (class "Default")
      (node (ref "FASE_R") (pin "1") (pinfunction "1_1") (pintype "passive"))
      (node (ref "R22") (pin "1") (pinfunction "1_1") (pintype "passive"))
      (node (ref "R27") (pin "2") (pinfunction "2_2") (pintype "passive"))
      (node (ref "T1") (pin "A1") (pinfunction "A1_A1") (pintype "passive"))
      (node (ref "TR2") (pin "8") (pinfunction "6_8") (pintype "passive"))
    )
    (net (code "66") (name "unconnected-(IC3-RA0{slash}AN0-Pad17)") (class "Default")
      (node (ref "IC3") (pin "17") (pinfunction "RA0/AN0_17") (pintype "bidirectional"))
    )
    (net (code "67") (name "unconnected-(IC3-RA1{slash}AN1-Pad18)") (class "Default")
      (node (ref "IC3") (pin "18") (pinfunction "RA1/AN1_18") (pintype "bidirectional"))
    )
    (net (code "68") (name "unconnected-(IC3-RB1{slash}RX{slash}DT-Pad7)") (class "Default")
      (node (ref "IC3") (pin "7") (pinfunction "RB1/RX/DT_7") (pintype "bidirectional"))
    )
    (net (code "69") (name "unconnected-(IC3-RB6{slash}T1OSO{slash}1ICKI{slash}PGC-Pad12)") (class "Default")
      (node (ref "IC3") (pin "12") (pinfunction "RB6/T1OSO/1ICKI/PGC_12") (pintype "bidirectional"))
    )
    (net (code "70") (name "unconnected-(IC3-RB7{slash}T1OSI{slash}PGD-Pad13)") (class "Default")
      (node (ref "IC3") (pin "13") (pinfunction "RB7/T1OSI/PGD_13") (pintype "bidirectional"))
    )
    (net (code "71") (name "unconnected-(K3B-S-Pad14)") (class "Default")
      (node (ref "K3") (pin "14") (pinfunction "S_14") (pintype "passive"))
    )
    (net (code "72") (name "unconnected-(OK1D-A-Pad8)") (class "Default")
      (node (ref "OK1") (pin "8") (pinfunction "A_8") (pintype "passive"))
    )
    (net (code "73") (name "unconnected-(OK1D-C-Pad7)") (class "Default")
      (node (ref "OK1") (pin "7") (pinfunction "C_7") (pintype "passive"))
    )
    (net (code "74") (name "unconnected-(OK1D-COL-Pad10)") (class "Default")
      (node (ref "OK1") (pin "10") (pinfunction "COL_10") (pintype "passive"))
    )
    (net (code "75") (name "unconnected-(OK1D-EMI-Pad9)") (class "Default")
      (node (ref "OK1") (pin "9") (pinfunction "EMI_9") (pintype "passive"))
    )
    (net (code "76") (name "unconnected-(TR1-3-Pad5)") (class "Default")
      (node (ref "TR1") (pin "5") (pinfunction "3_5") (pintype "passive"))
    )
    (net (code "77") (name "unconnected-(TR1-4-Pad6)") (class "Default")
      (node (ref "TR1") (pin "6") (pinfunction "4_6") (pintype "passive"))
    )
    (net (code "78") (name "unconnected-(TR2-3-Pad5)") (class "Default")
      (node (ref "TR2") (pin "5") (pinfunction "3_5") (pintype "passive"))
    )
    (net (code "79") (name "unconnected-(TR2-4-Pad6)") (class "Default")
      (node (ref "TR2") (pin "6") (pinfunction "4_6") (pintype "passive"))
    )
    (net (code "80") (name "unconnected-(TR3-3-Pad5)") (class "Default")
      (node (ref "TR3") (pin "5") (pinfunction "3_5") (pintype "passive"))
    )
    (net (code "81") (name "unconnected-(TR3-4-Pad6)") (class "Default")
      (node (ref "TR3") (pin "6") (pinfunction "4_6") (pintype "passive"))
    )
  )
)
